# FlashAdapter_mmc5.net
KiCad netlist of a schematic drawn in EAGLE
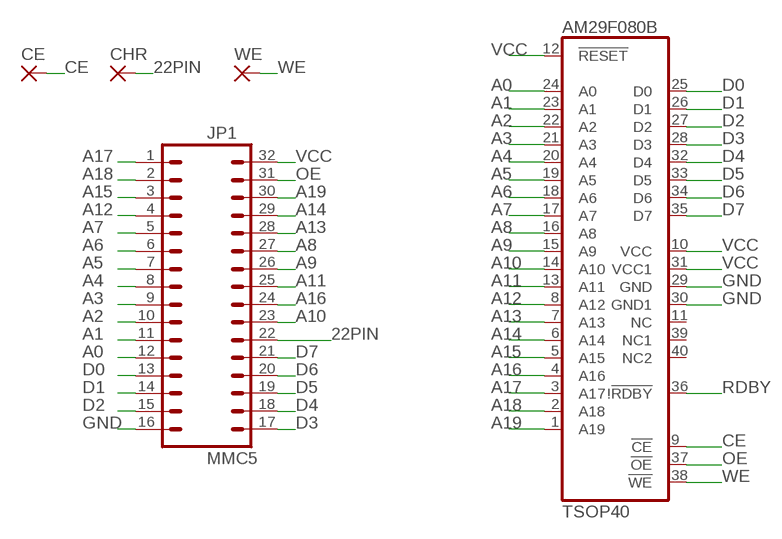
[diagram p0: schematic, sheet 1]

(export (version "E")
  (design (tool "Eeschema 10.0.6"))
  (components
    (comp (ref "AM29F080B")
      (value "TSOP40")
      (footprint "eagle-import:TSOP40")
      (libsource (lib "eagle-import") (part "TSOP40"))
    )
    (comp (ref "CE")
      (value "SMD2")
      (footprint "eagle-import:SMD1,27-2,54")
      (libsource (lib "eagle-import") (part "SMD2"))
    )
    (comp (ref "CHR")
      (value "SMD2")
      (footprint "eagle-import:SMD1,27-2,54")
      (libsource (lib "eagle-import") (part "SMD2"))
    )
    (comp (ref "JP1")
      (value "MMC5")
      (footprint "eagle-import:DIP32")
      (libsource (lib "eagle-import") (part "DIP32PTH"))
    )
    (comp (ref "WE")
      (value "SMD2")
      (footprint "eagle-import:SMD1,27-2,54")
      (libsource (lib "eagle-import") (part "SMD2"))
    )
  )
  (nets
    (net (code "1") (name "/22PIN") (class "Default")
      (node (ref "CHR") (pin "1") (pinfunction "P_1") (pintype "passive"))
      (node (ref "JP1") (pin "22") (pinfunction "22_22") (pintype "passive"))
    )
    (net (code "2") (name "/A0") (class "Default")
      (node (ref "AM29F080B") (pin "24") (pinfunction "A0_24") (pintype "input"))
      (node (ref "JP1") (pin "12") (pinfunction "12_12") (pintype "passive"))
    )
    (net (code "3") (name "/A1") (class "Default")
      (node (ref "AM29F080B") (pin "23") (pinfunction "A1_23") (pintype "input"))
      (node (ref "JP1") (pin "11") (pinfunction "11_11") (pintype "passive"))
    )
    (net (code "4") (name "/A2") (class "Default")
      (node (ref "AM29F080B") (pin "22") (pinfunction "A2_22") (pintype "input"))
      (node (ref "JP1") (pin "10") (pinfunction "10_10") (pintype "passive"))
    )
    (net (code "5") (name "/A3") (class "Default")
      (node (ref "AM29F080B") (pin "21") (pinfunction "A3_21") (pintype "input"))
      (node (ref "JP1") (pin "9") (pinfunction "9_9") (pintype "passive"))
    )
    (net (code "6") (name "/A4") (class "Default")
      (node (ref "AM29F080B") (pin "20") (pinfunction "A4_20") (pintype "input"))
      (node (ref "JP1") (pin "8") (pinfunction "8_8") (pintype "passive"))
    )
    (net (code "7") (name "/A5") (class "Default")
      (node (ref "AM29F080B") (pin "19") (pinfunction "A5_19") (pintype "input"))
      (node (ref "JP1") (pin "7") (pinfunction "7_7") (pintype "passive"))
    )
    (net (code "8") (name "/A6") (class "Default")
      (node (ref "AM29F080B") (pin "18") (pinfunction "A6_18") (pintype "input"))
      (node (ref "JP1") (pin "6") (pinfunction "6_6") (pintype "passive"))
    )
    (net (code "9") (name "/A7") (class "Default")
      (node (ref "AM29F080B") (pin "17") (pinfunction "A7_17") (pintype "input"))
      (node (ref "JP1") (pin "5") (pinfunction "5_5") (pintype "passive"))
    )
    (net (code "10") (name "/A8") (class "Default")
      (node (ref "AM29F080B") (pin "16") (pinfunction "A8_16") (pintype "input"))
      (node (ref "JP1") (pin "27") (pinfunction "27_27") (pintype "passive"))
    )
    (net (code "11") (name "/A9") (class "Default")
      (node (ref "AM29F080B") (pin "15") (pinfunction "A9_15") (pintype "input"))
      (node (ref "JP1") (pin "26") (pinfunction "26_26") (pintype "passive"))
    )
    (net (code "12") (name "/A10") (class "Default")
      (node (ref "AM29F080B") (pin "14") (pinfunction "A10_14") (pintype "input"))
      (node (ref "JP1") (pin "23") (pinfunction "23_23") (pintype "passive"))
    )
    (net (code "13") (name "/A11") (class "Default")
      (node (ref "AM29F080B") (pin "13") (pinfunction "A11_13") (pintype "input"))
      (node (ref "JP1") (pin "25") (pinfunction "25_25") (pintype "passive"))
    )
    (net (code "14") (name "/A12") (class "Default")
      (node (ref "AM29F080B") (pin "8") (pinfunction "A12_8") (pintype "input"))
      (node (ref "JP1") (pin "4") (pinfunction "4_4") (pintype "passive"))
    )
    (net (code "15") (name "/A13") (class "Default")
      (node (ref "AM29F080B") (pin "7") (pinfunction "A13_7") (pintype "input"))
      (node (ref "JP1") (pin "28") (pinfunction "28_28") (pintype "passive"))
    )
    (net (code "16") (name "/A14") (class "Default")
      (node (ref "AM29F080B") (pin "6") (pinfunction "A14_6") (pintype "input"))
      (node (ref "JP1") (pin "29") (pinfunction "29_29") (pintype "passive"))
    )
    (net (code "17") (name "/A15") (class "Default")
      (node (ref "AM29F080B") (pin "5") (pinfunction "A15_5") (pintype "input"))
      (node (ref "JP1") (pin "3") (pinfunction "3_3") (pintype "passive"))
    )
    (net (code "18") (name "/A16") (class "Default")
      (node (ref "AM29F080B") (pin "4") (pinfunction "A16_4") (pintype "input"))
      (node (ref "JP1") (pin "24") (pinfunction "24_24") (pintype "passive"))
    )
    (net (code "19") (name "/A17") (class "Default")
      (node (ref "AM29F080B") (pin "3") (pinfunction "A17_3") (pintype "input"))
      (node (ref "JP1") (pin "1") (pinfunction "1_1") (pintype "passive"))
    )
    (net (code "20") (name "/A18") (class "Default")
      (node (ref "AM29F080B") (pin "2") (pinfunction "A18_2") (pintype "input"))
      (node (ref "JP1") (pin "2") (pinfunction "2_2") (pintype "passive"))
    )
    (net (code "21") (name "/A19") (class "Default")
      (node (ref "AM29F080B") (pin "1") (pinfunction "A19_1") (pintype "input"))
      (node (ref "JP1") (pin "30") (pinfunction "30_30") (pintype "passive"))
    )
    (net (code "22") (name "/CE") (class "Default")
      (node (ref "AM29F080B") (pin "9") (pinfunction "~{CE}_9") (pintype "input"))
      (node (ref "CE") (pin "1") (pinfunction "P_1") (pintype "passive"))
    )
    (net (code "23") (name "/D0") (class "Default")
      (node (ref "AM29F080B") (pin "25") (pinfunction "D0_25") (pintype "tri_state"))
      (node (ref "JP1") (pin "13") (pinfunction "13_13") (pintype "passive"))
    )
    (net (code "24") (name "/D1") (class "Default")
      (node (ref "AM29F080B") (pin "26") (pinfunction "D1_26") (pintype "tri_state"))
      (node (ref "JP1") (pin "14") (pinfunction "14_14") (pintype "passive"))
    )
    (net (code "25") (name "/D2") (class "Default")
      (node (ref "AM29F080B") (pin "27") (pinfunction "D2_27") (pintype "tri_state"))
      (node (ref "JP1") (pin "15") (pinfunction "15_15") (pintype "passive"))
    )
    (net (code "26") (name "/D3") (class "Default")
      (node (ref "AM29F080B") (pin "28") (pinfunction "D3_28") (pintype "tri_state"))
      (node (ref "JP1") (pin "17") (pinfunction "17_17") (pintype "passive"))
    )
    (net (code "27") (name "/D4") (class "Default")
      (node (ref "AM29F080B") (pin "32") (pinfunction "D4_32") (pintype "tri_state"))
      (node (ref "JP1") (pin "18") (pinfunction "18_18") (pintype "passive"))
    )
    (net (code "28") (name "/D5") (class "Default")
      (node (ref "AM29F080B") (pin "33") (pinfunction "D5_33") (pintype "tri_state"))
      (node (ref "JP1") (pin "19") (pinfunction "19_19") (pintype "passive"))
    )
    (net (code "29") (name "/D6") (class "Default")
      (node (ref "AM29F080B") (pin "34") (pinfunction "D6_34") (pintype "tri_state"))
      (node (ref "JP1") (pin "20") (pinfunction "20_20") (pintype "passive"))
    )
    (net (code "30") (name "/D7") (class "Default")
      (node (ref "AM29F080B") (pin "35") (pinfunction "D7_35") (pintype "tri_state"))
      (node (ref "JP1") (pin "21") (pinfunction "21_21") (pintype "passive"))
    )
    (net (code "31") (name "/GND") (class "Default")
      (node (ref "AM29F080B") (pin "29") (pinfunction "GND_29") (pintype "output"))
      (node (ref "AM29F080B") (pin "30") (pinfunction "GND1_30") (pintype "output"))
      (node (ref "JP1") (pin "16") (pinfunction "16_16") (pintype "passive"))
    )
    (net (code "32") (name "/OE") (class "Default")
      (node (ref "AM29F080B") (pin "37") (pinfunction "~{OE}_37") (pintype "input"))
      (node (ref "JP1") (pin "31") (pinfunction "31_31") (pintype "passive"))
    )
    (net (code "33") (name "/RDBY") (class "Default")
      (node (ref "AM29F080B") (pin "36") (pinfunction "~RDBY_36") (pintype "output"))
    )
    (net (code "34") (name "/VCC") (class "Default")
      (node (ref "AM29F080B") (pin "10") (pinfunction "VCC_10") (pintype "output"))
      (node (ref "AM29F080B") (pin "12") (pinfunction "~{RESET}_12") (pintype "input"))
      (node (ref "AM29F080B") (pin "31") (pinfunction "VCC1_31") (pintype "output"))
      (node (ref "JP1") (pin "32") (pinfunction "32_32") (pintype "passive"))
    )
    (net (code "35") (name "/WE") (class "Default")
      (node (ref "AM29F080B") (pin "38") (pinfunction "~{WE}_38") (pintype "input"))
      (node (ref "WE") (pin "1") (pinfunction "P_1") (pintype "passive"))
    )
    (net (code "36") (name "unconnected-(AM29F080B-NC-Pad11)") (class "Default")
      (node (ref "AM29F080B") (pin "11") (pinfunction "NC_11") (pintype "output"))
    )
    (net (code "37") (name "unconnected-(AM29F080B-NC1-Pad39)") (class "Default")
      (node (ref "AM29F080B") (pin "39") (pinfunction "NC1_39") (pintype "output"))
    )
    (net (code "38") (name "unconnected-(AM29F080B-NC2-Pad40)") (class "Default")
      (node (ref "AM29F080B") (pin "40") (pinfunction "NC2_40") (pintype "output"))
    )
  )
)
